# uJOVE_BleedFix.net
KiCad netlist of a schematic drawn in EAGLE
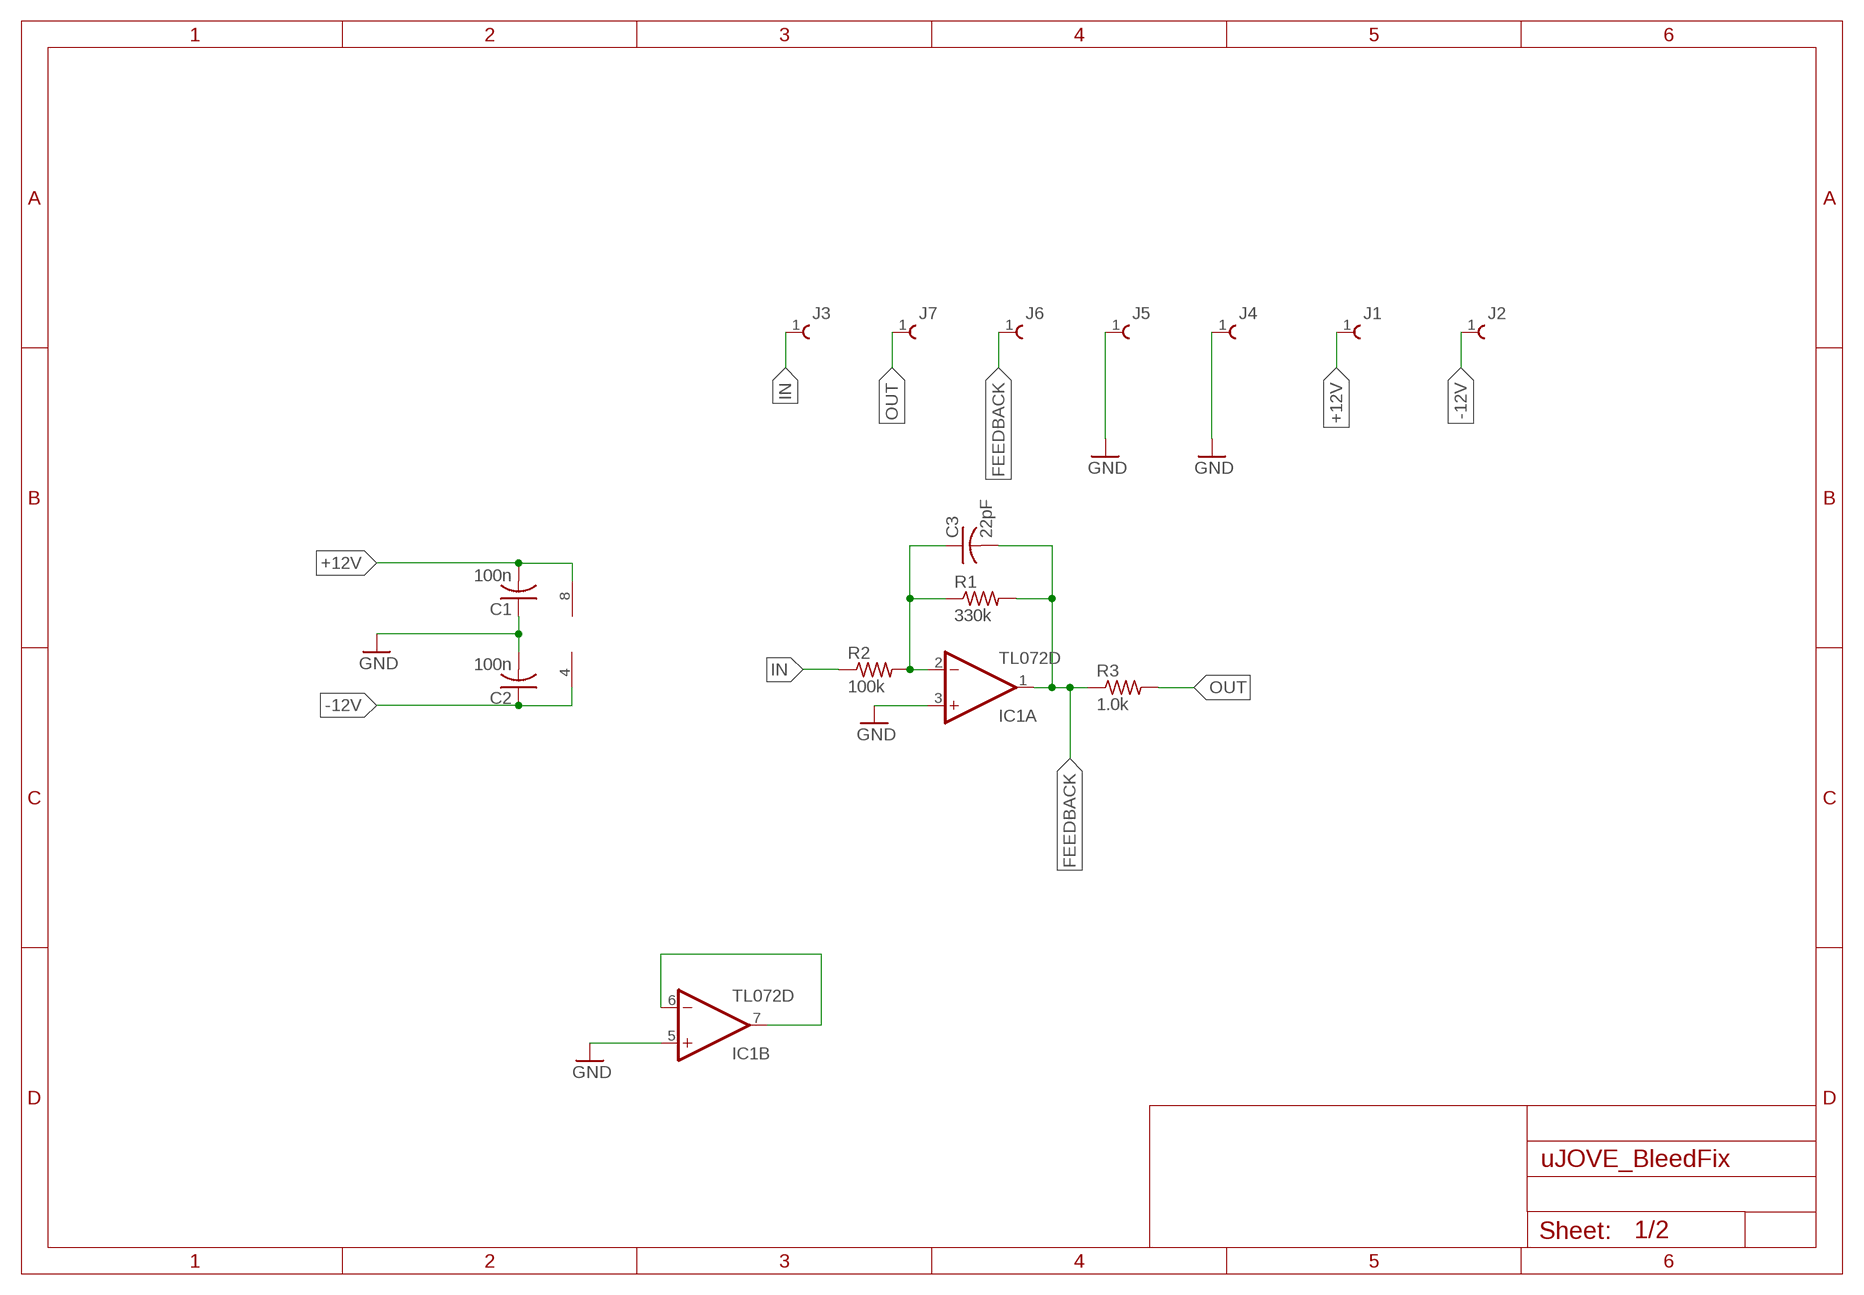
[diagram p0: schematic, sheet 1]

(export (version "E")
  (design (tool "Eeschema 10.0.6"))
  (components
    (comp (ref "C1")
      (value "100n")
      (footprint "eagle-import:C0603")
      (libsource (lib "eagle-import") (part "C-USC0603"))
    )
    (comp (ref "C2")
      (value "100n")
      (footprint "eagle-import:C0603")
      (libsource (lib "eagle-import") (part "C-USC0603"))
    )
    (comp (ref "C3")
      (value "22pF")
      (footprint "eagle-import:C0603")
      (libsource (lib "eagle-import") (part "C-USC0603"))
    )
    (comp (ref "IC1")
      (value "TL072D")
      (footprint "eagle-import:SO08")
      (libsource (lib "eagle-import") (part "TL072D"))
    )
    (comp (ref "J1")
      (value "61300111121")
      (footprint "eagle-import:61300111121")
      (libsource (lib "eagle-import") (part "61300111121"))
    )
    (comp (ref "J2")
      (value "61300111121")
      (footprint "eagle-import:61300111121")
      (libsource (lib "eagle-import") (part "61300111121"))
    )
    (comp (ref "J3")
      (value "61300111121")
      (footprint "eagle-import:61300111121")
      (libsource (lib "eagle-import") (part "61300111121"))
    )
    (comp (ref "J4")
      (value "61300111121")
      (footprint "eagle-import:61300111121")
      (libsource (lib "eagle-import") (part "61300111121"))
    )
    (comp (ref "J5")
      (value "61300111121")
      (footprint "eagle-import:61300111121")
      (libsource (lib "eagle-import") (part "61300111121"))
    )
    (comp (ref "J6")
      (value "61300111121")
      (footprint "eagle-import:61300111121")
      (libsource (lib "eagle-import") (part "61300111121"))
    )
    (comp (ref "J7")
      (value "61300111121")
      (footprint "eagle-import:61300111121")
      (libsource (lib "eagle-import") (part "61300111121"))
    )
    (comp (ref "R1")
      (value "330k")
      (footprint "eagle-import:R0603")
      (libsource (lib "eagle-import") (part "R-US_R0603"))
    )
    (comp (ref "R2")
      (value "100k")
      (footprint "eagle-import:R0603")
      (libsource (lib "eagle-import") (part "R-US_R0603"))
    )
    (comp (ref "R3")
      (value "1.0k")
      (footprint "eagle-import:R0603")
      (libsource (lib "eagle-import") (part "R-US_R0603"))
    )
  )
  (nets
    (net (code "1") (name "+12V") (class "Default")
      (node (ref "C1") (pin "2") (pinfunction "2_2") (pintype "passive"))
      (node (ref "IC1") (pin "8") (pinfunction "V+_8") (pintype "power_in"))
      (node (ref "J1") (pin "1") (pinfunction "1_1") (pintype "passive"))
    )
    (net (code "2") (name "-12V") (class "Default")
      (node (ref "C2") (pin "1") (pinfunction "1_1") (pintype "passive"))
      (node (ref "IC1") (pin "4") (pinfunction "V-_4") (pintype "power_in"))
      (node (ref "J2") (pin "1") (pinfunction "1_1") (pintype "passive"))
    )
    (net (code "3") (name "FEEDBACK") (class "Default")
      (node (ref "C3") (pin "2") (pinfunction "2_2") (pintype "passive"))
      (node (ref "IC1") (pin "1") (pinfunction "OUT_1") (pintype "output"))
      (node (ref "J6") (pin "1") (pinfunction "1_1") (pintype "passive"))
      (node (ref "R1") (pin "2") (pinfunction "2_2") (pintype "passive"))
      (node (ref "R3") (pin "1") (pinfunction "1_1") (pintype "passive"))
    )
    (net (code "4") (name "GND") (class "Default")
      (node (ref "C1") (pin "1") (pinfunction "1_1") (pintype "passive"))
      (node (ref "C2") (pin "2") (pinfunction "2_2") (pintype "passive"))
      (node (ref "IC1") (pin "3") (pinfunction "+IN_3") (pintype "input"))
      (node (ref "IC1") (pin "5") (pinfunction "+IN_5") (pintype "input"))
      (node (ref "J4") (pin "1") (pinfunction "1_1") (pintype "passive"))
      (node (ref "J5") (pin "1") (pinfunction "1_1") (pintype "passive"))
    )
    (net (code "5") (name "IN") (class "Default")
      (node (ref "J3") (pin "1") (pinfunction "1_1") (pintype "passive"))
      (node (ref "R2") (pin "1") (pinfunction "1_1") (pintype "passive"))
    )
    (net (code "6") (name "Net-(IC1A--IN)") (class "Default")
      (node (ref "C3") (pin "1") (pinfunction "1_1") (pintype "passive"))
      (node (ref "IC1") (pin "2") (pinfunction "-IN_2") (pintype "input"))
      (node (ref "R1") (pin "1") (pinfunction "1_1") (pintype "passive"))
      (node (ref "R2") (pin "2") (pinfunction "2_2") (pintype "passive"))
    )
    (net (code "7") (name "Net-(IC1B--IN)") (class "Default")
      (node (ref "IC1") (pin "6") (pinfunction "-IN_6") (pintype "input"))
      (node (ref "IC1") (pin "7") (pinfunction "OUT_7") (pintype "output"))
    )
    (net (code "8") (name "OUT") (class "Default")
      (node (ref "J7") (pin "1") (pinfunction "1_1") (pintype "passive"))
      (node (ref "R3") (pin "2") (pinfunction "2_2") (pintype "passive"))
    )
  )
)
